# Prijemnik.net
KiCad netlist of a schematic drawn in Altium Designer
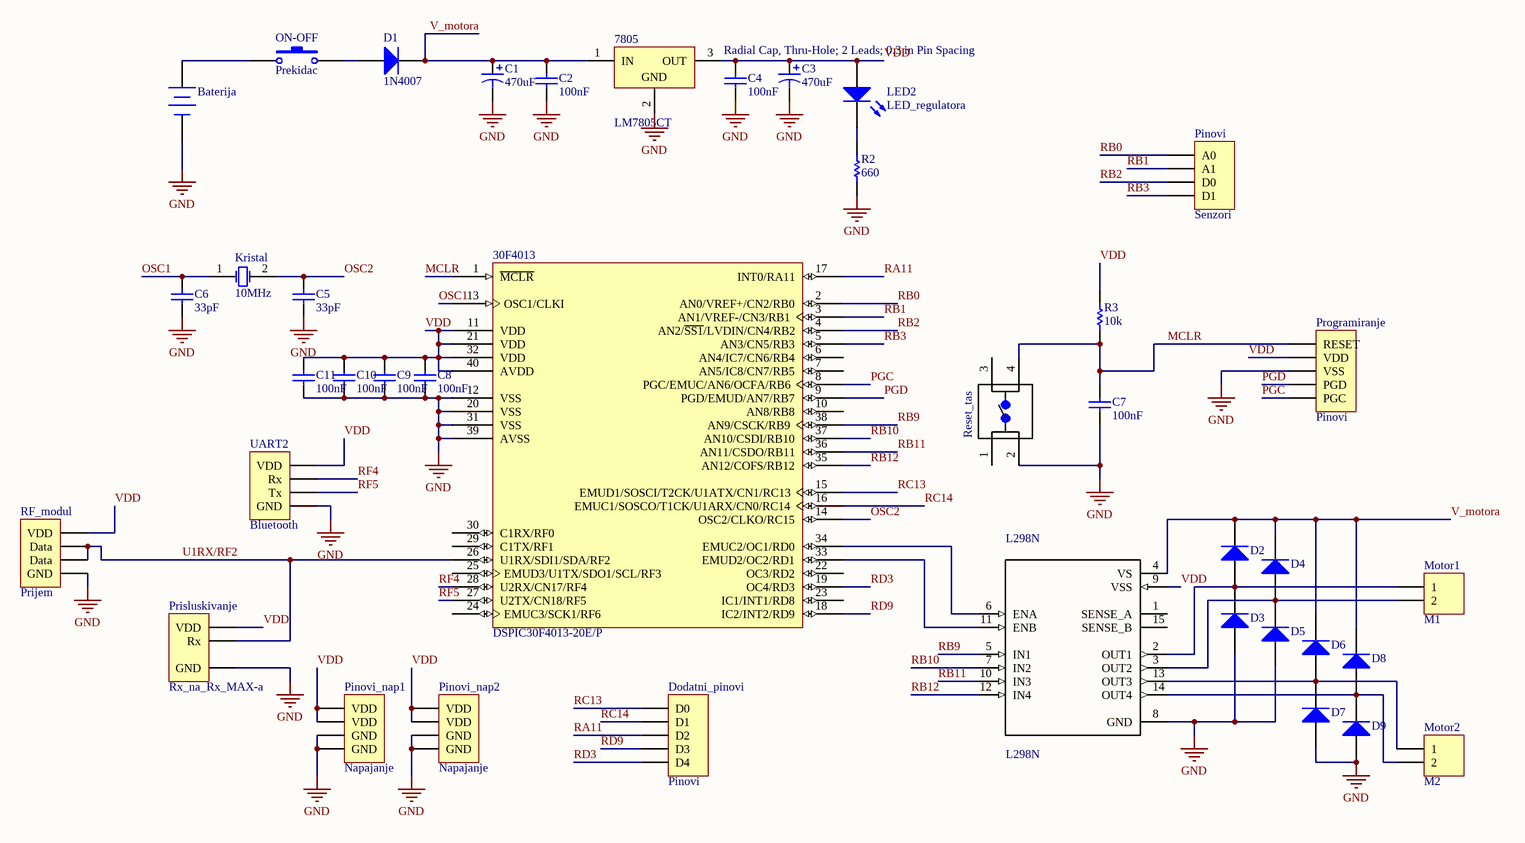
[diagram p0: Prijemnik.SchDoc]

(export (version "E")
  (design (tool "Eeschema 10.0.6"))
  (components
    (comp (ref "30F4013")
      (value "DSPIC30F4013-20E/P")
      (footprint "PDIP600-P40")
      (fields (field (name "PUBLISHER") "Altium Limited"))
      (libsource (lib "Microchip DSC 16-Bit dsPIC30F") (part "DSPIC30F4013-20E/P"))
    )
    (comp (ref "7805")
      (value "LM7805CT")
      (footprint "T03B")
      (description "3-Terminal Negative Regulator, 3-pin TO-220")
      (fields
        (field (name "PARTNUMBER") "LM7905CT")
        (field (name "MANUFACTURER") "National Semiconductor")
        (field (name "PUBLISHER") "Altium Limited")
      )
      (libsource (lib "NSC LDO") (part "LM7905CT"))
    )
    (comp (ref "Baterija")
      (value "9V")
      (footprint "BAT-2")
      (description "Multicell Battery")
      (fields (field (name "PUBLISHER") "Altium Limited"))
      (libsource (lib "Miscellaneous Devices") (part "Battery"))
    )
    (comp (ref "C1")
      (value "470uF")
      (footprint "El. Kondenzator 470uf")
      (description "Polarized Capacitor (Radial)")
      (fields (field (name "PUBLISHER") "Altium Limited"))
      (libsource (lib "Miscellaneous Devices") (part "Cap Pol1"))
    )
    (comp (ref "C2")
      (value "100nF")
      (footprint "C blok 100n")
      (description "Capacitor")
      (fields (field (name "PUBLISHER") "Altium Limited"))
      (libsource (lib "Miscellaneous Devices") (part "Cap"))
    )
    (comp (ref "C3")
      (value "470uF")
      (footprint "El. Kondenzator 470uf")
      (description "Polarized Capacitor (Radial)")
      (fields (field (name "PUBLISHER") "Altium Limited"))
      (libsource (lib "Miscellaneous Devices") (part "Cap Pol1"))
    )
    (comp (ref "C4")
      (value "100nF")
      (footprint "C blok 100n")
      (description "Capacitor")
      (fields
        (field (name "PACKAGEDESCRIPTION") "Radial Cap, Thru-Hole; 2 Leads; 0.3 in Pin Spacing")
        (field (name "PUBLISHER") "Altium Limited")
      )
      (libsource (lib "Miscellaneous Devices") (part "Cap"))
    )
    (comp (ref "C5")
      (value "33pF")
      (footprint "C keramicki 30pF")
      (description "Capacitor")
      (fields (field (name "PUBLISHER") "Altium Limited"))
      (libsource (lib "Miscellaneous Devices") (part "Cap"))
    )
    (comp (ref "C6")
      (value "33pF")
      (footprint "C keramicki 30pF")
      (description "Capacitor")
      (fields (field (name "PUBLISHER") "Altium Limited"))
      (libsource (lib "Miscellaneous Devices") (part "Cap"))
    )
    (comp (ref "C7")
      (value "100nF")
      (footprint "C blok 100n")
      (description "Capacitor")
      (fields (field (name "PUBLISHER") "Altium Limited"))
      (libsource (lib "Miscellaneous Devices") (part "Cap"))
    )
    (comp (ref "C8")
      (value "100nF")
      (footprint "C blok 100n")
      (description "Capacitor")
      (fields (field (name "PUBLISHER") "Altium Limited"))
      (libsource (lib "Miscellaneous Devices") (part "Cap"))
    )
    (comp (ref "C9")
      (value "100nF")
      (footprint "C blok 100n")
      (description "Capacitor")
      (fields (field (name "PUBLISHER") "Altium Limited"))
      (libsource (lib "Miscellaneous Devices") (part "Cap"))
    )
    (comp (ref "C10")
      (value "100nF")
      (footprint "C blok 100n")
      (description "Capacitor")
      (fields (field (name "PUBLISHER") "Altium Limited"))
      (libsource (lib "Miscellaneous Devices") (part "Cap"))
    )
    (comp (ref "C11")
      (value "100nF")
      (footprint "C blok 100n")
      (description "Capacitor")
      (fields (field (name "PUBLISHER") "Altium Limited"))
      (libsource (lib "Miscellaneous Devices") (part "Cap"))
    )
    (comp (ref "D1")
      (value "1N4007")
      (footprint "DO-41")
      (description "1 Amp General Purpose Rectifier")
      (fields (field (name "PUBLISHER") "Altium Limited"))
      (libsource (lib "Miscellaneous Devices") (part "Diode 1N4007"))
    )
    (comp (ref "D2")
      (value "Diode 1N4007")
      (footprint "DO-41")
      (description "1 Amp General Purpose Rectifier")
      (fields (field (name "PUBLISHER") "Altium Limited"))
      (libsource (lib "Miscellaneous Devices") (part "Diode 1N4007"))
    )
    (comp (ref "D3")
      (value "Diode 1N4007")
      (footprint "DO-41")
      (description "1 Amp General Purpose Rectifier")
      (fields (field (name "PUBLISHER") "Altium Limited"))
      (libsource (lib "Miscellaneous Devices") (part "Diode 1N4007"))
    )
    (comp (ref "D4")
      (value "Diode 1N4007")
      (footprint "DO-41")
      (description "1 Amp General Purpose Rectifier")
      (fields (field (name "PUBLISHER") "Altium Limited"))
      (libsource (lib "Miscellaneous Devices") (part "Diode 1N4007"))
    )
    (comp (ref "D5")
      (value "Diode 1N4007")
      (footprint "DO-41")
      (description "1 Amp General Purpose Rectifier")
      (fields (field (name "PUBLISHER") "Altium Limited"))
      (libsource (lib "Miscellaneous Devices") (part "Diode 1N4007"))
    )
    (comp (ref "D6")
      (value "Diode 1N4007")
      (footprint "DO-41")
      (description "1 Amp General Purpose Rectifier")
      (fields (field (name "PUBLISHER") "Altium Limited"))
      (libsource (lib "Miscellaneous Devices") (part "Diode 1N4007"))
    )
    (comp (ref "D7")
      (value "Diode 1N4007")
      (footprint "DO-41")
      (description "1 Amp General Purpose Rectifier")
      (fields (field (name "PUBLISHER") "Altium Limited"))
      (libsource (lib "Miscellaneous Devices") (part "Diode 1N4007"))
    )
    (comp (ref "D8")
      (value "Diode 1N4007")
      (footprint "DO-41")
      (description "1 Amp General Purpose Rectifier")
      (fields (field (name "PUBLISHER") "Altium Limited"))
      (libsource (lib "Miscellaneous Devices") (part "Diode 1N4007"))
    )
    (comp (ref "D9")
      (value "Diode 1N4007")
      (footprint "DO-41")
      (description "1 Amp General Purpose Rectifier")
      (fields (field (name "PUBLISHER") "Altium Limited"))
      (libsource (lib "Miscellaneous Devices") (part "Diode 1N4007"))
    )
    (comp (ref "Dodatni_pinovi")
      (value "Pinovi")
      (footprint "HDR1X5")
      (description "Header, 5-Pin")
      (fields (field (name "PUBLISHER") "Altium Limited"))
      (libsource (lib "Miscellaneous Connectors") (part "Header 5"))
    )
    (comp (ref "Kristal")
      (value "10MHz")
      (footprint "R38")
      (description "Crystal Oscillator")
      (fields (field (name "PUBLISHER") "Altium Limited"))
      (libsource (lib "Miscellaneous Devices") (part "XTAL"))
    )
    (comp (ref "L298N")
      (value "L298N")
      (footprint "*TO127P2020X500X2100-15")
      (description "Half Bridge _4_ Driver DC Motors, Relays, Solenoids, Stepper Motors Bipolar 15-Multiwatt")
      (fields (field (name "MF") "STMicroelectronics"))
      (libsource (lib "L298N") (part "L298N"))
    )
    (comp (ref "LED2")
      (value "LED_regulatora")
      (footprint "LED_5mm")
      (description "Typical RED GaAs LED")
      (fields (field (name "PUBLISHER") "Altium Limited"))
      (libsource (lib "Miscellaneous Devices") (part "LED1"))
    )
    (comp (ref "Motor1")
      (value "M1")
      (footprint "HDR1X2")
      (description "Header, 2-Pin")
      (fields (field (name "PUBLISHER") "Altium Limited"))
      (libsource (lib "Miscellaneous Connectors") (part "Header 2"))
    )
    (comp (ref "Motor2")
      (value "M2")
      (footprint "HDR1X2")
      (description "Header, 2-Pin")
      (fields (field (name "PUBLISHER") "Altium Limited"))
      (libsource (lib "Miscellaneous Connectors") (part "Header 2"))
    )
    (comp (ref "ON-OFF")
      (value "Prekidac")
      (footprint "SPST-2")
      (description "Switch")
      (fields (field (name "PUBLISHER") "Altium Limited"))
      (libsource (lib "Miscellaneous Devices") (part "SW-PB"))
    )
    (comp (ref "Pinovi")
      (value "Senzori")
      (footprint "HDR1X4")
      (description "Header, 4-Pin")
      (fields (field (name "PUBLISHER") "Altium Limited"))
      (libsource (lib "") (part "Header 4_1"))
    )
    (comp (ref "Pinovi_nap1")
      (value "Napajanje")
      (footprint "HDR1X4")
      (description "Header, 4-Pin")
      (fields (field (name "PUBLISHER") "Altium Limited"))
      (libsource (lib "") (part "Header 4_2"))
    )
    (comp (ref "Pinovi_nap2")
      (value "Napajanje")
      (footprint "HDR1X4")
      (description "Header, 4-Pin")
      (fields (field (name "PUBLISHER") "Altium Limited"))
      (libsource (lib "") (part "Header 4_2"))
    )
    (comp (ref "Prisluskivanje")
      (value "Rx_na_Rx_MAX-a")
      (footprint "HDR1X3")
      (description "Header, 4-Pin")
      (fields (field (name "PUBLISHER") "Altium Limited"))
      (libsource (lib "") (part "Header 4_3"))
    )
    (comp (ref "Programiranje")
      (value "Pinovi")
      (footprint "HDR1X5")
      (description "Header, 5-Pin")
      (fields (field (name "PUBLISHER") "Altium Limited"))
      (libsource (lib "Miscellaneous Connectors") (part "Header 5"))
    )
    (comp (ref "R2")
      (value "660")
      (footprint "AXIAL-0.3")
      (description "Resistor")
      (fields (field (name "PUBLISHER") "Altium Limited"))
      (libsource (lib "Miscellaneous Devices") (part "Res1"))
    )
    (comp (ref "R3")
      (value "10k")
      (footprint "AXIAL-0.3")
      (description "Resistor")
      (fields (field (name "PUBLISHER") "Altium Limited"))
      (libsource (lib "Miscellaneous Devices") (part "Res1"))
    )
    (comp (ref "Reset_tas")
      (value "3-1825910-1")
      (footprint "*TE_3-1825910-1")
      (description "Switch Push Button OFF _ON_ SPST Round Button 0.05A 24VDC Momentary Contact PC Pins Thru-Hole")
      (fields (field (name "MF") "TE Connectivity"))
      (libsource (lib "3-1825910-1") (part "3-1825910-1"))
    )
    (comp (ref "RF_modul")
      (value "Prijem")
      (footprint "HDR1X4")
      (description "Header, 4-Pin")
      (fields (field (name "PUBLISHER") "Altium Limited"))
      (libsource (lib "Miscellaneous Connectors") (part "Header 4"))
    )
    (comp (ref "UART2")
      (value "Bluetooth")
      (footprint "HDR1X4")
      (description "Header, 4-Pin")
      (fields (field (name "PUBLISHER") "Altium Limited"))
      (libsource (lib "Miscellaneous Connectors") (part "Header 4"))
    )
  )
  (nets
    (net (code "1") (name "/MCLR") (class "Default")
      (node (ref "30F4013") (pin "1") (pinfunction "~{MCLR}_1") (pintype "input"))
      (node (ref "C7") (pin "2") (pinfunction "2_2") (pintype "passive"))
      (node (ref "Programiranje") (pin "1") (pinfunction "RESET_1") (pintype "passive"))
      (node (ref "R3") (pin "1") (pinfunction "1_1") (pintype "passive"))
      (node (ref "Reset_tas") (pin "4") (pinfunction "4_4") (pintype "passive"))
    )
    (net (code "2") (name "/OSC1") (class "Default")
      (node (ref "30F4013") (pin "13") (pinfunction "OSC1/CLKI_13") (pintype "input"))
      (node (ref "C6") (pin "2") (pinfunction "2_2") (pintype "passive"))
      (node (ref "Kristal") (pin "1") (pinfunction "OSC1_1") (pintype "passive"))
    )
    (net (code "3") (name "/OSC2") (class "Default")
      (node (ref "30F4013") (pin "14") (pinfunction "OSC2/CLKO/RC15_14") (pintype "bidirectional"))
      (node (ref "C5") (pin "2") (pinfunction "2_2") (pintype "passive"))
      (node (ref "Kristal") (pin "2") (pinfunction "OSC2_2") (pintype "passive"))
    )
    (net (code "4") (name "/PGC") (class "Default")
      (node (ref "30F4013") (pin "8") (pinfunction "PGC/EMUC/AN6/OCFA/RB6_8") (pintype "bidirectional"))
      (node (ref "Programiranje") (pin "5") (pinfunction "PGC_5") (pintype "passive"))
    )
    (net (code "5") (name "/PGD") (class "Default")
      (node (ref "30F4013") (pin "9") (pinfunction "PGD/EMUD/AN7/RB7_9") (pintype "bidirectional"))
      (node (ref "Programiranje") (pin "4") (pinfunction "PGD_4") (pintype "passive"))
    )
    (net (code "6") (name "/RA11") (class "Default")
      (node (ref "30F4013") (pin "17") (pinfunction "INT0/RA11_17") (pintype "bidirectional"))
      (node (ref "Dodatni_pinovi") (pin "3") (pinfunction "VSS_3") (pintype "passive"))
    )
    (net (code "7") (name "/RB0") (class "Default")
      (node (ref "30F4013") (pin "2") (pinfunction "AN0/VREF+/CN2/RB0_2") (pintype "bidirectional"))
      (node (ref "Pinovi") (pin "1") (pinfunction "A0_1") (pintype "passive"))
    )
    (net (code "8") (name "/RB1") (class "Default")
      (node (ref "30F4013") (pin "3") (pinfunction "AN1/VREF-/CN3/RB1_3") (pintype "bidirectional"))
      (node (ref "Pinovi") (pin "2") (pinfunction "A1_2") (pintype "passive"))
    )
    (net (code "9") (name "/RB2") (class "Default")
      (node (ref "30F4013") (pin "4") (pinfunction "AN2/~{SS1}/LVDIN/CN4/RB2_4") (pintype "bidirectional"))
      (node (ref "Pinovi") (pin "3") (pinfunction "D0_3") (pintype "passive"))
    )
    (net (code "10") (name "/RB3") (class "Default")
      (node (ref "30F4013") (pin "5") (pinfunction "AN3/CN5/RB3_5") (pintype "bidirectional"))
      (node (ref "Pinovi") (pin "4") (pinfunction "D1_4") (pintype "passive"))
    )
    (net (code "11") (name "/RB9") (class "Default")
      (node (ref "30F4013") (pin "38") (pinfunction "AN9/CSCK/RB9_38") (pintype "bidirectional"))
      (node (ref "L298N") (pin "5") (pinfunction "IN1_5") (pintype "input"))
    )
    (net (code "12") (name "/RB10") (class "Default")
      (node (ref "30F4013") (pin "37") (pinfunction "AN10/CSDI/RB10_37") (pintype "bidirectional"))
      (node (ref "L298N") (pin "7") (pinfunction "IN2_7") (pintype "input"))
    )
    (net (code "13") (name "/RB11") (class "Default")
      (node (ref "30F4013") (pin "36") (pinfunction "AN11/CSDO/RB11_36") (pintype "bidirectional"))
      (node (ref "L298N") (pin "10") (pinfunction "IN3_10") (pintype "input"))
    )
    (net (code "14") (name "/RB12") (class "Default")
      (node (ref "30F4013") (pin "35") (pinfunction "AN12/COFS/RB12_35") (pintype "bidirectional"))
      (node (ref "L298N") (pin "12") (pinfunction "IN4_12") (pintype "input"))
    )
    (net (code "15") (name "/RC13") (class "Default")
      (node (ref "30F4013") (pin "15") (pinfunction "EMUD1/SOSCI/T2CK/U1ATX/CN1/RC13_15") (pintype "bidirectional"))
      (node (ref "Dodatni_pinovi") (pin "1") (pinfunction "RESET_1") (pintype "passive"))
    )
    (net (code "16") (name "/RC14") (class "Default")
      (node (ref "30F4013") (pin "16") (pinfunction "EMUC1/SOSCO/T1CK/U1ARX/CN0/RC14_16") (pintype "bidirectional"))
      (node (ref "Dodatni_pinovi") (pin "2") (pinfunction "VDD_2") (pintype "passive"))
    )
    (net (code "17") (name "/RD3") (class "Default")
      (node (ref "30F4013") (pin "19") (pinfunction "OC4/RD3_19") (pintype "bidirectional"))
      (node (ref "Dodatni_pinovi") (pin "5") (pinfunction "PGC_5") (pintype "passive"))
    )
    (net (code "18") (name "/RD9") (class "Default")
      (node (ref "30F4013") (pin "18") (pinfunction "IC2/INT2/RD9_18") (pintype "bidirectional"))
      (node (ref "Dodatni_pinovi") (pin "4") (pinfunction "PGD_4") (pintype "passive"))
    )
    (net (code "19") (name "/RF4") (class "Default")
      (node (ref "30F4013") (pin "28") (pinfunction "U2RX/CN17/RF4_28") (pintype "bidirectional"))
      (node (ref "UART2") (pin "2") (pinfunction "Data_2") (pintype "passive"))
    )
    (net (code "20") (name "/RF5") (class "Default")
      (node (ref "30F4013") (pin "27") (pinfunction "U2TX/CN18/RF5_27") (pintype "bidirectional"))
      (node (ref "UART2") (pin "3") (pinfunction "Data_3") (pintype "passive"))
    )
    (net (code "21") (name "/U1RX{slash}RF2") (class "Default")
      (node (ref "30F4013") (pin "26") (pinfunction "U1RX/SDI1/SDA/RF2_26") (pintype "bidirectional"))
      (node (ref "Prisluskivanje") (pin "2") (pinfunction "Rx_2") (pintype "passive"))
      (node (ref "RF_modul") (pin "2") (pinfunction "Data_2") (pintype "passive"))
      (node (ref "RF_modul") (pin "3") (pinfunction "Data_3") (pintype "passive"))
    )
    (net (code "22") (name "/VDD") (class "Default")
      (node (ref "30F4013") (pin "11") (pinfunction "VDD_11") (pintype "power_in"))
      (node (ref "30F4013") (pin "21") (pinfunction "VDD_21") (pintype "power_in"))
      (node (ref "30F4013") (pin "32") (pinfunction "VDD_32") (pintype "power_in"))
      (node (ref "30F4013") (pin "40") (pinfunction "AVDD_40") (pintype "power_in"))
      (node (ref "7805") (pin "3") (pinfunction "OUT_3") (pintype "power_in"))
      (node (ref "C10") (pin "2") (pinfunction "2_2") (pintype "passive"))
      (node (ref "C11") (pin "2") (pinfunction "2_2") (pintype "passive"))
      (node (ref "C3") (pin "1") (pinfunction "1_1") (pintype "passive"))
      (node (ref "C4") (pin "2") (pinfunction "2_2") (pintype "passive"))
      (node (ref "C8") (pin "2") (pinfunction "2_2") (pintype "passive"))
      (node (ref "C9") (pin "2") (pinfunction "2_2") (pintype "passive"))
      (node (ref "L298N") (pin "9") (pinfunction "VSS_9") (pintype "input"))
      (node (ref "LED2") (pin "1") (pinfunction "A_1") (pintype "passive"))
      (node (ref "Pinovi_nap1") (pin "1") (pinfunction "VDD_1") (pintype "passive"))
      (node (ref "Pinovi_nap1") (pin "2") (pinfunction "VDD_2") (pintype "passive"))
      (node (ref "Pinovi_nap2") (pin "1") (pinfunction "VDD_1") (pintype "passive"))
      (node (ref "Pinovi_nap2") (pin "2") (pinfunction "VDD_2") (pintype "passive"))
      (node (ref "Prisluskivanje") (pin "1") (pinfunction "VDD_1") (pintype "passive"))
      (node (ref "Programiranje") (pin "2") (pinfunction "VDD_2") (pintype "passive"))
      (node (ref "R3") (pin "2") (pinfunction "2_2") (pintype "passive"))
      (node (ref "RF_modul") (pin "1") (pinfunction "VDD_1") (pintype "passive"))
      (node (ref "UART2") (pin "1") (pinfunction "VDD_1") (pintype "passive"))
    )
    (net (code "23") (name "/V_motora") (class "Default")
      (node (ref "7805") (pin "1") (pinfunction "IN_1") (pintype "power_in"))
      (node (ref "C1") (pin "1") (pinfunction "1_1") (pintype "passive"))
      (node (ref "C2") (pin "2") (pinfunction "2_2") (pintype "passive"))
      (node (ref "D1") (pin "2") (pinfunction "K_2") (pintype "passive"))
      (node (ref "D2") (pin "2") (pinfunction "K_2") (pintype "passive"))
      (node (ref "D4") (pin "2") (pinfunction "K_2") (pintype "passive"))
      (node (ref "D6") (pin "2") (pinfunction "K_2") (pintype "passive"))
      (node (ref "D8") (pin "2") (pinfunction "K_2") (pintype "passive"))
      (node (ref "L298N") (pin "4") (pinfunction "VS_4") (pintype "power_in"))
    )
    (net (code "24") (name "GND") (class "Default")
      (node (ref "30F4013") (pin "12") (pinfunction "VSS_12") (pintype "power_in"))
      (node (ref "30F4013") (pin "20") (pinfunction "VSS_20") (pintype "power_in"))
      (node (ref "30F4013") (pin "31") (pinfunction "VSS_31") (pintype "power_in"))
      (node (ref "30F4013") (pin "39") (pinfunction "AVSS_39") (pintype "power_in"))
      (node (ref "7805") (pin "2") (pinfunction "GND_2") (pintype "power_in"))
      (node (ref "Baterija") (pin "2") (pinfunction "-_2") (pintype "passive"))
      (node (ref "C1") (pin "2") (pinfunction "2_2") (pintype "passive"))
      (node (ref "C10") (pin "1") (pinfunction "1_1") (pintype "passive"))
      (node (ref "C11") (pin "1") (pinfunction "1_1") (pintype "passive"))
      (node (ref "C2") (pin "1") (pinfunction "1_1") (pintype "passive"))
      (node (ref "C3") (pin "2") (pinfunction "2_2") (pintype "passive"))
      (node (ref "C4") (pin "1") (pinfunction "1_1") (pintype "passive"))
      (node (ref "C5") (pin "1") (pinfunction "1_1") (pintype "passive"))
      (node (ref "C6") (pin "1") (pinfunction "1_1") (pintype "passive"))
      (node (ref "C7") (pin "1") (pinfunction "1_1") (pintype "passive"))
      (node (ref "C8") (pin "1") (pinfunction "1_1") (pintype "passive"))
      (node (ref "C9") (pin "1") (pinfunction "1_1") (pintype "passive"))
      (node (ref "D3") (pin "1") (pinfunction "A_1") (pintype "passive"))
      (node (ref "D5") (pin "1") (pinfunction "A_1") (pintype "passive"))
      (node (ref "D7") (pin "1") (pinfunction "A_1") (pintype "passive"))
      (node (ref "D9") (pin "1") (pinfunction "A_1") (pintype "passive"))
      (node (ref "L298N") (pin "8") (pinfunction "GND_8") (pintype "power_in"))
      (node (ref "Pinovi_nap1") (pin "3") (pinfunction "GND_3") (pintype "passive"))
      (node (ref "Pinovi_nap1") (pin "4") (pinfunction "GND_4") (pintype "passive"))
      (node (ref "Pinovi_nap2") (pin "3") (pinfunction "GND_3") (pintype "passive"))
      (node (ref "Pinovi_nap2") (pin "4") (pinfunction "GND_4") (pintype "passive"))
      (node (ref "Prisluskivanje") (pin "3") (pinfunction "GND_3") (pintype "passive"))
      (node (ref "Programiranje") (pin "3") (pinfunction "VSS_3") (pintype "passive"))
      (node (ref "R2") (pin "1") (pinfunction "1_1") (pintype "passive"))
      (node (ref "RF_modul") (pin "4") (pinfunction "GND_4") (pintype "passive"))
      (node (ref "Reset_tas") (pin "2") (pinfunction "2_2") (pintype "passive"))
      (node (ref "UART2") (pin "4") (pinfunction "GND_4") (pintype "passive"))
    )
    (net (code "25") (name "Net-(30F4013-EMUC2{slash}OC1{slash}RD0)") (class "Default")
      (node (ref "30F4013") (pin "34") (pinfunction "EMUC2/OC1/RD0_34") (pintype "bidirectional"))
      (node (ref "L298N") (pin "6") (pinfunction "ENA_6") (pintype "input"))
    )
    (net (code "26") (name "Net-(30F4013-EMUD2{slash}OC2{slash}RD1)") (class "Default")
      (node (ref "30F4013") (pin "33") (pinfunction "EMUD2/OC2/RD1_33") (pintype "bidirectional"))
      (node (ref "L298N") (pin "11") (pinfunction "ENB_11") (pintype "input"))
    )
    (net (code "27") (name "Net-(Baterija-+)") (class "Default")
      (node (ref "Baterija") (pin "1") (pinfunction "+_1") (pintype "passive"))
      (node (ref "ON-OFF") (pin "1") (pinfunction "1_1") (pintype "passive"))
    )
    (net (code "28") (name "Net-(D1-A)") (class "Default")
      (node (ref "D1") (pin "1") (pinfunction "A_1") (pintype "passive"))
      (node (ref "ON-OFF") (pin "2") (pinfunction "2_2") (pintype "passive"))
    )
    (net (code "29") (name "Net-(D2-A)") (class "Default")
      (node (ref "D2") (pin "1") (pinfunction "A_1") (pintype "passive"))
      (node (ref "D3") (pin "2") (pinfunction "K_2") (pintype "passive"))
      (node (ref "L298N") (pin "2") (pinfunction "OUT1_2") (pintype "output"))
      (node (ref "Motor1") (pin "1") (pinfunction "1_1") (pintype "passive"))
    )
    (net (code "30") (name "Net-(D4-A)") (class "Default")
      (node (ref "D4") (pin "1") (pinfunction "A_1") (pintype "passive"))
      (node (ref "D5") (pin "2") (pinfunction "K_2") (pintype "passive"))
      (node (ref "L298N") (pin "3") (pinfunction "OUT2_3") (pintype "output"))
      (node (ref "Motor1") (pin "2") (pinfunction "2_2") (pintype "passive"))
    )
    (net (code "31") (name "Net-(D6-A)") (class "Default")
      (node (ref "D6") (pin "1") (pinfunction "A_1") (pintype "passive"))
      (node (ref "D7") (pin "2") (pinfunction "K_2") (pintype "passive"))
      (node (ref "L298N") (pin "13") (pinfunction "OUT3_13") (pintype "output"))
      (node (ref "Motor2") (pin "1") (pinfunction "1_1") (pintype "passive"))
    )
    (net (code "32") (name "Net-(D8-A)") (class "Default")
      (node (ref "D8") (pin "1") (pinfunction "A_1") (pintype "passive"))
      (node (ref "D9") (pin "2") (pinfunction "K_2") (pintype "passive"))
      (node (ref "L298N") (pin "14") (pinfunction "OUT4_14") (pintype "output"))
      (node (ref "Motor2") (pin "2") (pinfunction "2_2") (pintype "passive"))
    )
    (net (code "33") (name "Net-(LED2-K)") (class "Default")
      (node (ref "LED2") (pin "2") (pinfunction "K_2") (pintype "passive"))
      (node (ref "R2") (pin "2") (pinfunction "2_2") (pintype "passive"))
    )
    (net (code "34") (name "unconnected-(30F4013-AN4{slash}IC7{slash}CN6{slash}RB4-Pad6)") (class "Default")
      (node (ref "30F4013") (pin "6") (pinfunction "AN4/IC7/CN6/RB4_6") (pintype "bidirectional"))
    )
    (net (code "35") (name "unconnected-(30F4013-AN5{slash}IC8{slash}CN7{slash}RB5-Pad7)") (class "Default")
      (node (ref "30F4013") (pin "7") (pinfunction "AN5/IC8/CN7/RB5_7") (pintype "bidirectional"))
    )
    (net (code "36") (name "unconnected-(30F4013-AN8{slash}RB8-Pad10)") (class "Default")
      (node (ref "30F4013") (pin "10") (pinfunction "AN8/RB8_10") (pintype "bidirectional"))
    )
    (net (code "37") (name "unconnected-(30F4013-C1RX{slash}RF0-Pad30)") (class "Default")
      (node (ref "30F4013") (pin "30") (pinfunction "C1RX/RF0_30") (pintype "bidirectional"))
    )
    (net (code "38") (name "unconnected-(30F4013-C1TX{slash}RF1-Pad29)") (class "Default")
      (node (ref "30F4013") (pin "29") (pinfunction "C1TX/RF1_29") (pintype "bidirectional"))
    )
    (net (code "39") (name "unconnected-(30F4013-EMUC3{slash}SCK1{slash}RF6-Pad24)") (class "Default")
      (node (ref "30F4013") (pin "24") (pinfunction "EMUC3/SCK1/RF6_24") (pintype "bidirectional"))
    )
    (net (code "40") (name "unconnected-(30F4013-EMUD3{slash}U1TX{slash}SDO1{slash}SCL{slash}RF3-Pad25)") (class "Default")
      (node (ref "30F4013") (pin "25") (pinfunction "EMUD3/U1TX/SDO1/SCL/RF3_25") (pintype "bidirectional"))
    )
    (net (code "41") (name "unconnected-(30F4013-IC1{slash}INT1{slash}RD8-Pad23)") (class "Default")
      (node (ref "30F4013") (pin "23") (pinfunction "IC1/INT1/RD8_23") (pintype "bidirectional"))
    )
    (net (code "42") (name "unconnected-(30F4013-OC3{slash}RD2-Pad22)") (class "Default")
      (node (ref "30F4013") (pin "22") (pinfunction "OC3/RD2_22") (pintype "bidirectional"))
    )
    (net (code "43") (name "unconnected-(L298N-SENSE_A-Pad1)") (class "Default")
      (node (ref "L298N") (pin "1") (pinfunction "SENSE_A_1") (pintype "passive"))
    )
    (net (code "44") (name "unconnected-(L298N-SENSE_B-Pad15)") (class "Default")
      (node (ref "L298N") (pin "15") (pinfunction "SENSE_B_15") (pintype "passive"))
    )
    (net (code "45") (name "unconnected-(Reset_tas-Pad1)") (class "Default")
      (node (ref "Reset_tas") (pin "1") (pinfunction "1_1") (pintype "passive"))
    )
    (net (code "46") (name "unconnected-(Reset_tas-Pad3)") (class "Default")
      (node (ref "Reset_tas") (pin "3") (pinfunction "3_3") (pintype "passive"))
    )
  )
)
